# HomeAutomation.net
KiCad netlist of a schematic drawn in EAGLE
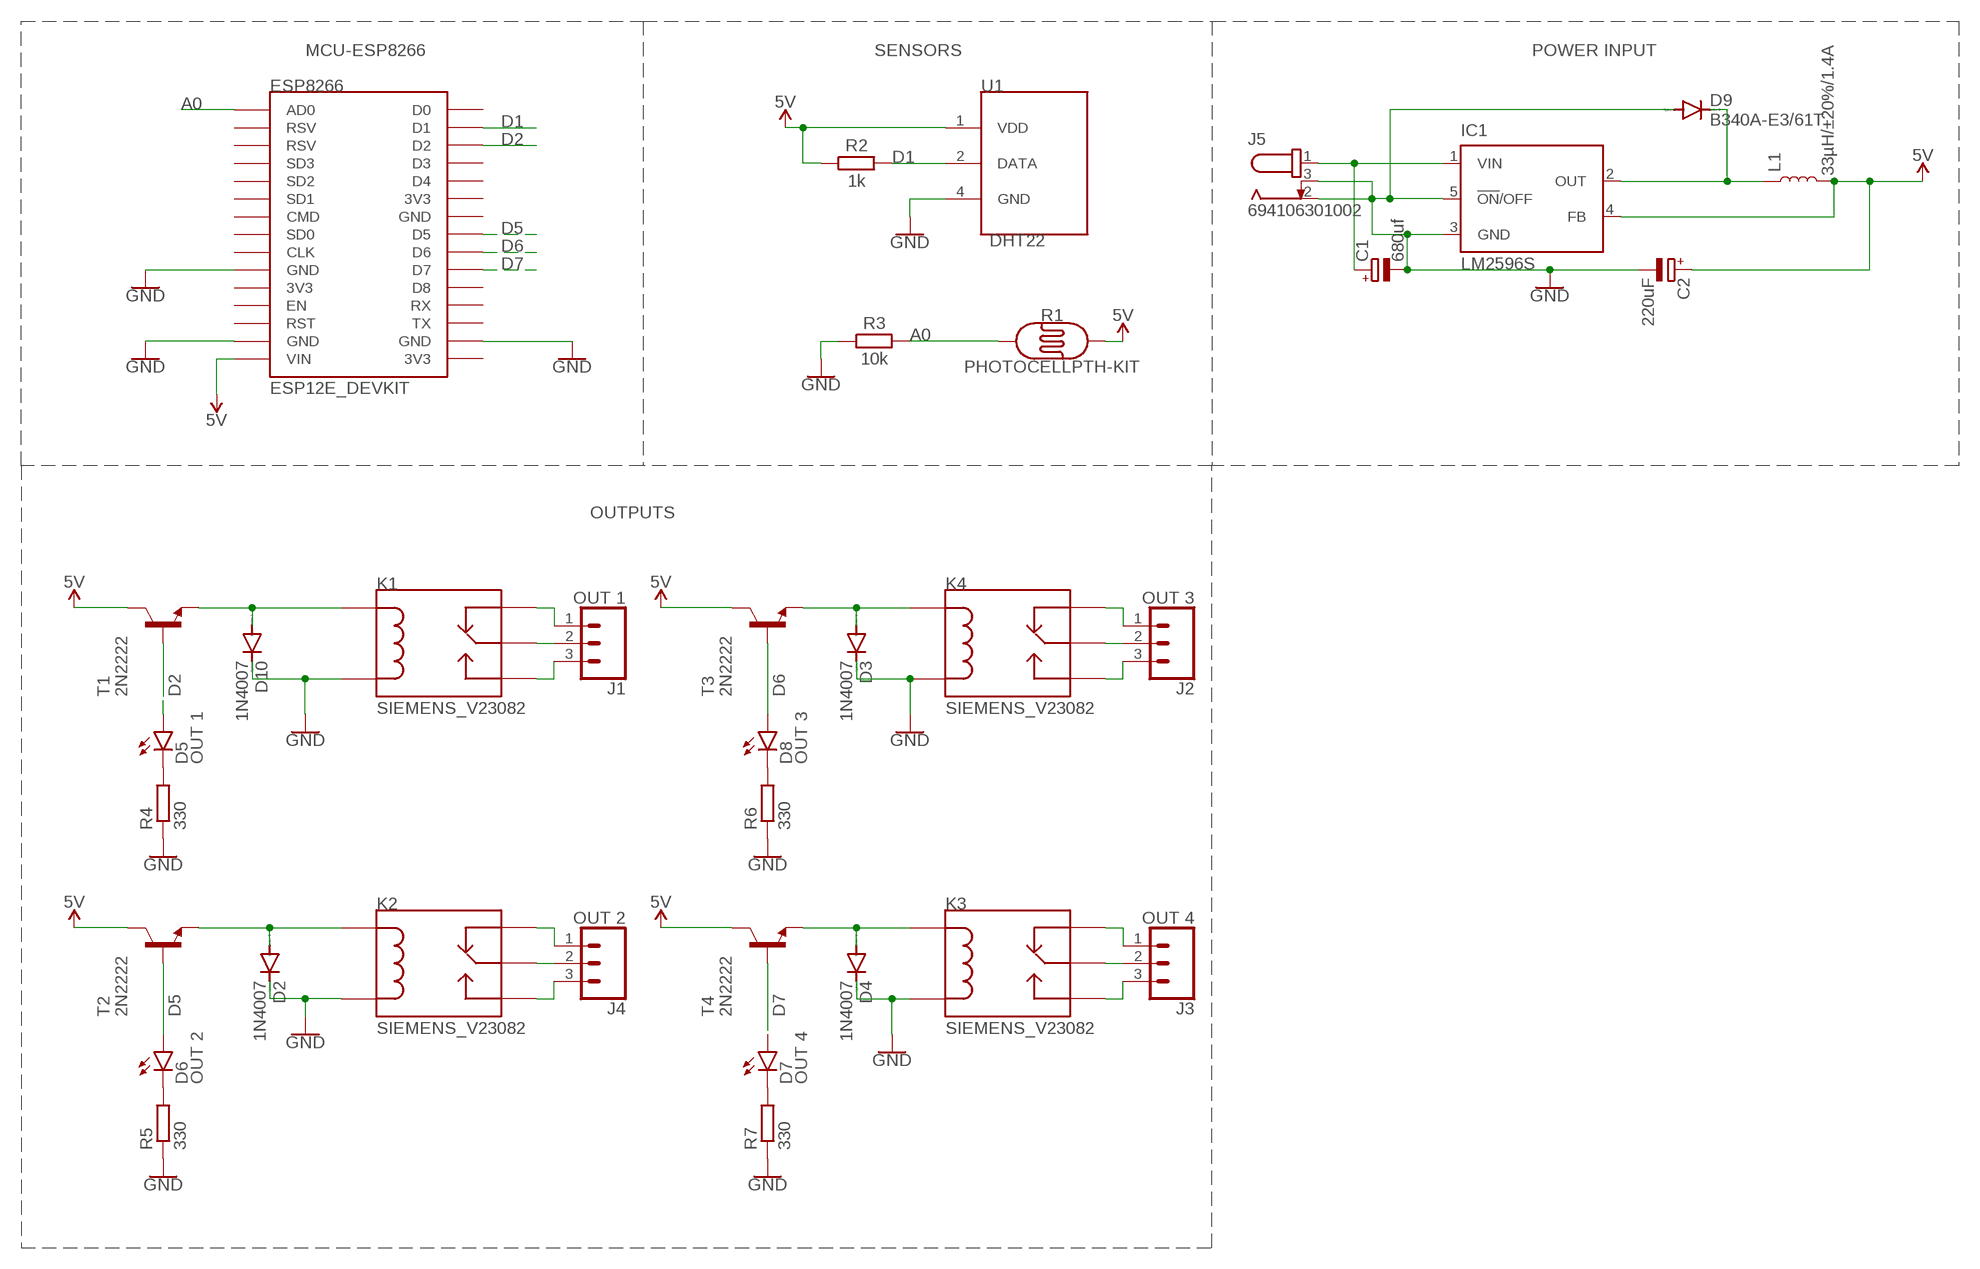
[diagram p0: schematic, sheet 1]

(export (version "E")
  (design (tool "Eeschema 10.0.6"))
  (components
    (comp (ref "C1")
      (value "680uf")
      (footprint "eagle-import:153CLV-0405")
      (libsource (lib "eagle-import") (part "CPOL-EU153CLV-0405"))
    )
    (comp (ref "C2")
      (value "220uF")
      (footprint "eagle-import:153CLV-0405")
      (libsource (lib "eagle-import") (part "CPOL-EU153CLV-0405"))
    )
    (comp (ref "D2")
      (value "1N4007")
      (footprint "eagle-import:DO214AC")
      (libsource (lib "eagle-import") (part "DIODE-DO214AC"))
    )
    (comp (ref "D3")
      (value "1N4007")
      (footprint "eagle-import:DO214AC")
      (libsource (lib "eagle-import") (part "DIODE-DO214AC"))
    )
    (comp (ref "D4")
      (value "1N4007")
      (footprint "eagle-import:DO214AC")
      (libsource (lib "eagle-import") (part "DIODE-DO214AC"))
    )
    (comp (ref "D5")
      (value "OUT 1")
      (footprint "eagle-import:CHIPLED_1206")
      (libsource (lib "eagle-import") (part "LEDCHIPLED_1206"))
    )
    (comp (ref "D6")
      (value "OUT 2")
      (footprint "eagle-import:CHIPLED_1206")
      (libsource (lib "eagle-import") (part "LEDCHIPLED_1206"))
    )
    (comp (ref "D7")
      (value "OUT 4")
      (footprint "eagle-import:CHIPLED_1206")
      (libsource (lib "eagle-import") (part "LEDCHIPLED_1206"))
    )
    (comp (ref "D8")
      (value "OUT 3")
      (footprint "eagle-import:CHIPLED_1206")
      (libsource (lib "eagle-import") (part "LEDCHIPLED_1206"))
    )
    (comp (ref "D9")
      (value "B340A-E3/61T")
      (footprint "eagle-import:DO214AC")
      (libsource (lib "eagle-import") (part "DIODE-DO214AC"))
    )
    (comp (ref "D10")
      (value "1N4007")
      (footprint "eagle-import:DO214AC")
      (libsource (lib "eagle-import") (part "DIODE-DO214AC"))
    )
    (comp (ref "ESP8266")
      (value "ESP12E_DEVKIT")
      (footprint "eagle-import:ESP12E_DEVKIT")
      (libsource (lib "eagle-import") (part "ESP12E_DEVKIT"))
    )
    (comp (ref "IC1")
      (value "LM2596S")
      (footprint "eagle-import:TO263-5")
      (fields (field (name "MF") "NATIONAL SEMICONDUCTOR") (field (name "MPN") "LM2596S-ADJ/NOPB"))
      (libsource (lib "eagle-import") (part "LM2596S"))
    )
    (comp (ref "J1")
      (value "OUT 1")
      (footprint "eagle-import:SCREWTERMINAL-5MM-3")
      (libsource (lib "eagle-import") (part "CONN_03-SCREW-5MM"))
    )
    (comp (ref "J2")
      (value "OUT 3")
      (footprint "eagle-import:SCREWTERMINAL-5MM-3")
      (libsource (lib "eagle-import") (part "CONN_03-SCREW-5MM"))
    )
    (comp (ref "J3")
      (value "OUT 4")
      (footprint "eagle-import:SCREWTERMINAL-5MM-3")
      (libsource (lib "eagle-import") (part "CONN_03-SCREW-5MM"))
    )
    (comp (ref "J4")
      (value "OUT 2")
      (footprint "eagle-import:SCREWTERMINAL-5MM-3")
      (libsource (lib "eagle-import") (part "CONN_03-SCREW-5MM"))
    )
    (comp (ref "J5")
      (value "694106301002")
      (footprint "eagle-import:694106301002")
      (fields
        (field (name "DIGIKEY_PART_NUMBER") "732-5930-ND")
        (field (name "MANUFACTURER") "Wurth Electronics Inc.")
        (field (name "CREATED_BY") "PCBLayout.com")
      )
      (libsource (lib "eagle-import") (part "694106301002"))
    )
    (comp (ref "K1")
      (value "SIEMENS_V23082")
      (footprint "eagle-import:SIEMENS_V23082_RELAY")
      (libsource (lib "eagle-import") (part "SIEMENS_V23082_RELAY"))
    )
    (comp (ref "K2")
      (value "SIEMENS_V23082")
      (footprint "eagle-import:SIEMENS_V23082_RELAY")
      (libsource (lib "eagle-import") (part "SIEMENS_V23082_RELAY"))
    )
    (comp (ref "K3")
      (value "SIEMENS_V23082")
      (footprint "eagle-import:SIEMENS_V23082_RELAY")
      (libsource (lib "eagle-import") (part "SIEMENS_V23082_RELAY"))
    )
    (comp (ref "K4")
      (value "SIEMENS_V23082")
      (footprint "eagle-import:SIEMENS_V23082_RELAY")
      (libsource (lib "eagle-import") (part "SIEMENS_V23082_RELAY"))
    )
    (comp (ref "L1")
      (value "33µH/±20%/1.4A")
      (footprint "eagle-import:SRN6045")
      (libsource (lib "eagle-import") (part "INDUCTOR-SRN6045-33UH"))
    )
    (comp (ref "R1")
      (value "PHOTOCELLPTH-KIT")
      (footprint "eagle-import:PHOTOCELL-KIT")
      (libsource (lib "eagle-import") (part "PHOTOCELLPTH-KIT"))
    )
    (comp (ref "R2")
      (value "1k")
      (footprint "eagle-import:RESC1005X40")
      (libsource (lib "eagle-import") (part "RCHIP-0402(1005-METRIC)_"))
    )
    (comp (ref "R3")
      (value "10k")
      (footprint "eagle-import:RESC1005X40")
      (libsource (lib "eagle-import") (part "RCHIP-0402(1005-METRIC)_"))
    )
    (comp (ref "R4")
      (value "330")
      (footprint "eagle-import:R0805")
      (libsource (lib "eagle-import") (part "R-EU_R0805"))
    )
    (comp (ref "R5")
      (value "330")
      (footprint "eagle-import:R0805")
      (libsource (lib "eagle-import") (part "R-EU_R0805"))
    )
    (comp (ref "R6")
      (value "330")
      (footprint "eagle-import:R0805")
      (libsource (lib "eagle-import") (part "R-EU_R0805"))
    )
    (comp (ref "R7")
      (value "330")
      (footprint "eagle-import:R0805")
      (libsource (lib "eagle-import") (part "R-EU_R0805"))
    )
    (comp (ref "T1")
      (value "2N2222")
      (footprint "eagle-import:SOT23-BEC")
      (libsource (lib "eagle-import") (part "-NPN-SOT23-BECMMBT2222ALT1"))
    )
    (comp (ref "T2")
      (value "2N2222")
      (footprint "eagle-import:SOT23-BEC")
      (libsource (lib "eagle-import") (part "-NPN-SOT23-BECMMBT2222ALT1"))
    )
    (comp (ref "T3")
      (value "2N2222")
      (footprint "eagle-import:SOT23-BEC")
      (libsource (lib "eagle-import") (part "-NPN-SOT23-BECMMBT2222ALT1"))
    )
    (comp (ref "T4")
      (value "2N2222")
      (footprint "eagle-import:SOT23-BEC")
      (libsource (lib "eagle-import") (part "-NPN-SOT23-BECMMBT2222ALT1"))
    )
    (comp (ref "U1")
      (value "DHT22")
      (footprint "eagle-import:DHT22")
      (libsource (lib "eagle-import") (part "DHT22"))
    )
  )
  (nets
    (net (code "1") (name "/A0") (class "Default")
      (node (ref "ESP8266") (pin "AD0") (pinfunction "AD0_AD0") (pintype "bidirectional"))
      (node (ref "R1") (pin "1") (pinfunction "P$1_1") (pintype "bidirectional"))
      (node (ref "R3") (pin "2") (pinfunction "2_2") (pintype "passive"))
    )
    (net (code "2") (name "/D1") (class "Default")
      (node (ref "ESP8266") (pin "D1") (pinfunction "D1_D1") (pintype "bidirectional"))
      (node (ref "R2") (pin "2") (pinfunction "2_2") (pintype "passive"))
      (node (ref "U1") (pin "2") (pinfunction "DATA_2") (pintype "bidirectional"))
    )
    (net (code "3") (name "/D2") (class "Default")
      (node (ref "D5") (pin "A") (pinfunction "A_A") (pintype "passive"))
      (node (ref "ESP8266") (pin "D2") (pinfunction "D2_D2") (pintype "bidirectional"))
      (node (ref "T1") (pin "B") (pinfunction "B_B") (pintype "passive"))
    )
    (net (code "4") (name "/D5") (class "Default")
      (node (ref "D6") (pin "A") (pinfunction "A_A") (pintype "passive"))
      (node (ref "ESP8266") (pin "D5") (pinfunction "D5_D5") (pintype "bidirectional"))
      (node (ref "T2") (pin "B") (pinfunction "B_B") (pintype "passive"))
    )
    (net (code "5") (name "/D6") (class "Default")
      (node (ref "D8") (pin "A") (pinfunction "A_A") (pintype "passive"))
      (node (ref "ESP8266") (pin "D6") (pinfunction "D6_D6") (pintype "bidirectional"))
      (node (ref "T3") (pin "B") (pinfunction "B_B") (pintype "passive"))
    )
    (net (code "6") (name "/D7") (class "Default")
      (node (ref "D7") (pin "A") (pinfunction "A_A") (pintype "passive"))
      (node (ref "ESP8266") (pin "D7") (pinfunction "D7_D7") (pintype "bidirectional"))
      (node (ref "T4") (pin "B") (pinfunction "B_B") (pintype "passive"))
    )
    (net (code "7") (name "5V") (class "Default")
      (node (ref "C2") (pin "+") (pinfunction "+_+") (pintype "passive"))
      (node (ref "ESP8266") (pin "VIN") (pinfunction "VIN_VIN") (pintype "bidirectional"))
      (node (ref "IC1") (pin "4") (pinfunction "FB_4") (pintype "input"))
      (node (ref "L1") (pin "2") (pinfunction "2_2") (pintype "passive"))
      (node (ref "R1") (pin "2") (pinfunction "P$2_2") (pintype "bidirectional"))
      (node (ref "R2") (pin "1") (pinfunction "1_1") (pintype "passive"))
      (node (ref "T1") (pin "C") (pinfunction "C_C") (pintype "passive"))
      (node (ref "T2") (pin "C") (pinfunction "C_C") (pintype "passive"))
      (node (ref "T3") (pin "C") (pinfunction "C_C") (pintype "passive"))
      (node (ref "T4") (pin "C") (pinfunction "C_C") (pintype "passive"))
      (node (ref "U1") (pin "1") (pinfunction "VDD_1") (pintype "bidirectional"))
    )
    (net (code "8") (name "GND") (class "Default")
      (node (ref "C1") (pin "-") (pinfunction "-_-") (pintype "passive"))
      (node (ref "C2") (pin "-") (pinfunction "-_-") (pintype "passive"))
      (node (ref "D10") (pin "C") (pinfunction "C_C") (pintype "passive"))
      (node (ref "D2") (pin "C") (pinfunction "C_C") (pintype "passive"))
      (node (ref "D3") (pin "C") (pinfunction "C_C") (pintype "passive"))
      (node (ref "D4") (pin "C") (pinfunction "C_C") (pintype "passive"))
      (node (ref "D9") (pin "A") (pinfunction "A_A") (pintype "passive"))
      (node (ref "ESP8266") (pin "GND@0") (pinfunction "GND_GND@0") (pintype "bidirectional"))
      (node (ref "ESP8266") (pin "GND@1") (pinfunction "GND_GND@1") (pintype "bidirectional"))
      (node (ref "ESP8266") (pin "GND@3") (pinfunction "GND_GND@3") (pintype "bidirectional"))
      (node (ref "IC1") (pin "3") (pinfunction "GND_3") (pintype "power_in"))
      (node (ref "IC1") (pin "5") (pinfunction "~{ON}/OFF_5") (pintype "input"))
      (node (ref "J5") (pin "2") (pinfunction "2_2") (pintype "passive"))
      (node (ref "J5") (pin "3") (pinfunction "3_3") (pintype "passive"))
      (node (ref "K1") (pin "P$2") (pinfunction "P$2_P$2") (pintype "bidirectional"))
      (node (ref "K2") (pin "P$2") (pinfunction "P$2_P$2") (pintype "bidirectional"))
      (node (ref "K3") (pin "P$2") (pinfunction "P$2_P$2") (pintype "bidirectional"))
      (node (ref "K4") (pin "P$2") (pinfunction "P$2_P$2") (pintype "bidirectional"))
      (node (ref "R3") (pin "1") (pinfunction "1_1") (pintype "passive"))
      (node (ref "R4") (pin "1") (pinfunction "1_1") (pintype "passive"))
      (node (ref "R5") (pin "1") (pinfunction "1_1") (pintype "passive"))
      (node (ref "R6") (pin "1") (pinfunction "1_1") (pintype "passive"))
      (node (ref "R7") (pin "1") (pinfunction "1_1") (pintype "passive"))
      (node (ref "U1") (pin "4") (pinfunction "GND_4") (pintype "bidirectional"))
    )
    (net (code "9") (name "Net-(D2-PadA)") (class "Default")
      (node (ref "D2") (pin "A") (pinfunction "A_A") (pintype "passive"))
      (node (ref "K2") (pin "P$1") (pinfunction "P$1_P$1") (pintype "bidirectional"))
      (node (ref "T2") (pin "E") (pinfunction "E_E") (pintype "passive"))
    )
    (net (code "10") (name "Net-(D3-PadA)") (class "Default")
      (node (ref "D3") (pin "A") (pinfunction "A_A") (pintype "passive"))
      (node (ref "K4") (pin "P$1") (pinfunction "P$1_P$1") (pintype "bidirectional"))
      (node (ref "T3") (pin "E") (pinfunction "E_E") (pintype "passive"))
    )
    (net (code "11") (name "Net-(D4-PadA)") (class "Default")
      (node (ref "D4") (pin "A") (pinfunction "A_A") (pintype "passive"))
      (node (ref "K3") (pin "P$1") (pinfunction "P$1_P$1") (pintype "bidirectional"))
      (node (ref "T4") (pin "E") (pinfunction "E_E") (pintype "passive"))
    )
    (net (code "12") (name "Net-(D5-PadC)") (class "Default")
      (node (ref "D5") (pin "C") (pinfunction "C_C") (pintype "passive"))
      (node (ref "R4") (pin "2") (pinfunction "2_2") (pintype "passive"))
    )
    (net (code "13") (name "Net-(D6-PadC)") (class "Default")
      (node (ref "D6") (pin "C") (pinfunction "C_C") (pintype "passive"))
      (node (ref "R5") (pin "2") (pinfunction "2_2") (pintype "passive"))
    )
    (net (code "14") (name "Net-(D7-PadC)") (class "Default")
      (node (ref "D7") (pin "C") (pinfunction "C_C") (pintype "passive"))
      (node (ref "R7") (pin "2") (pinfunction "2_2") (pintype "passive"))
    )
    (net (code "15") (name "Net-(D8-PadC)") (class "Default")
      (node (ref "D8") (pin "C") (pinfunction "C_C") (pintype "passive"))
      (node (ref "R6") (pin "2") (pinfunction "2_2") (pintype "passive"))
    )
    (net (code "16") (name "Net-(D10-PadA)") (class "Default")
      (node (ref "D10") (pin "A") (pinfunction "A_A") (pintype "passive"))
      (node (ref "K1") (pin "P$1") (pinfunction "P$1_P$1") (pintype "bidirectional"))
      (node (ref "T1") (pin "E") (pinfunction "E_E") (pintype "passive"))
    )
    (net (code "17") (name "Net-(IC1-OUT)") (class "Default")
      (node (ref "D9") (pin "C") (pinfunction "C_C") (pintype "passive"))
      (node (ref "IC1") (pin "2") (pinfunction "OUT_2") (pintype "output"))
      (node (ref "L1") (pin "1") (pinfunction "1_1") (pintype "passive"))
    )
    (net (code "18") (name "Net-(IC1-VIN)") (class "Default")
      (node (ref "C1") (pin "+") (pinfunction "+_+") (pintype "passive"))
      (node (ref "IC1") (pin "1") (pinfunction "VIN_1") (pintype "input"))
      (node (ref "J5") (pin "1") (pinfunction "1_1") (pintype "passive"))
    )
    (net (code "19") (name "Net-(J1-Pad1)") (class "Default")
      (node (ref "J1") (pin "1") (pinfunction "1_1") (pintype "passive"))
      (node (ref "K1") (pin "P$5") (pinfunction "P$5_P$5") (pintype "bidirectional"))
    )
    (net (code "20") (name "Net-(J1-Pad2)") (class "Default")
      (node (ref "J1") (pin "2") (pinfunction "2_2") (pintype "passive"))
      (node (ref "K1") (pin "P$3") (pinfunction "P$3_P$3") (pintype "bidirectional"))
    )
    (net (code "21") (name "Net-(J1-Pad3)") (class "Default")
      (node (ref "J1") (pin "3") (pinfunction "3_3") (pintype "passive"))
      (node (ref "K1") (pin "P$4") (pinfunction "P$4_P$4") (pintype "bidirectional"))
    )
    (net (code "22") (name "Net-(J2-Pad1)") (class "Default")
      (node (ref "J2") (pin "1") (pinfunction "1_1") (pintype "passive"))
      (node (ref "K4") (pin "P$5") (pinfunction "P$5_P$5") (pintype "bidirectional"))
    )
    (net (code "23") (name "Net-(J2-Pad2)") (class "Default")
      (node (ref "J2") (pin "2") (pinfunction "2_2") (pintype "passive"))
      (node (ref "K4") (pin "P$3") (pinfunction "P$3_P$3") (pintype "bidirectional"))
    )
    (net (code "24") (name "Net-(J2-Pad3)") (class "Default")
      (node (ref "J2") (pin "3") (pinfunction "3_3") (pintype "passive"))
      (node (ref "K4") (pin "P$4") (pinfunction "P$4_P$4") (pintype "bidirectional"))
    )
    (net (code "25") (name "Net-(J3-Pad1)") (class "Default")
      (node (ref "J3") (pin "1") (pinfunction "1_1") (pintype "passive"))
      (node (ref "K3") (pin "P$5") (pinfunction "P$5_P$5") (pintype "bidirectional"))
    )
    (net (code "26") (name "Net-(J3-Pad2)") (class "Default")
      (node (ref "J3") (pin "2") (pinfunction "2_2") (pintype "passive"))
      (node (ref "K3") (pin "P$3") (pinfunction "P$3_P$3") (pintype "bidirectional"))
    )
    (net (code "27") (name "Net-(J3-Pad3)") (class "Default")
      (node (ref "J3") (pin "3") (pinfunction "3_3") (pintype "passive"))
      (node (ref "K3") (pin "P$4") (pinfunction "P$4_P$4") (pintype "bidirectional"))
    )
    (net (code "28") (name "Net-(J4-Pad1)") (class "Default")
      (node (ref "J4") (pin "1") (pinfunction "1_1") (pintype "passive"))
      (node (ref "K2") (pin "P$5") (pinfunction "P$5_P$5") (pintype "bidirectional"))
    )
    (net (code "29") (name "Net-(J4-Pad2)") (class "Default")
      (node (ref "J4") (pin "2") (pinfunction "2_2") (pintype "passive"))
      (node (ref "K2") (pin "P$3") (pinfunction "P$3_P$3") (pintype "bidirectional"))
    )
    (net (code "30") (name "Net-(J4-Pad3)") (class "Default")
      (node (ref "J4") (pin "3") (pinfunction "3_3") (pintype "passive"))
      (node (ref "K2") (pin "P$4") (pinfunction "P$4_P$4") (pintype "bidirectional"))
    )
    (net (code "31") (name "unconnected-(ESP8266-3V3-Pad3V3@0)") (class "Default")
      (node (ref "ESP8266") (pin "3V3@0") (pinfunction "3V3_3V3@0") (pintype "bidirectional"))
    )
    (net (code "32") (name "unconnected-(ESP8266-3V3-Pad3V3@1)") (class "Default")
      (node (ref "ESP8266") (pin "3V3@1") (pinfunction "3V3_3V3@1") (pintype "bidirectional"))
    )
    (net (code "33") (name "unconnected-(ESP8266-3V3-Pad3V3@2)") (class "Default")
      (node (ref "ESP8266") (pin "3V3@2") (pinfunction "3V3_3V3@2") (pintype "bidirectional"))
    )
    (net (code "34") (name "unconnected-(ESP8266-GND-PadGND@2)") (class "Default")
      (node (ref "ESP8266") (pin "GND@2") (pinfunction "GND_GND@2") (pintype "bidirectional"))
    )
    (net (code "35") (name "unconnected-(ESP8266-PadCLK)") (class "Default")
      (node (ref "ESP8266") (pin "CLK") (pinfunction "CLK_CLK") (pintype "bidirectional"))
    )
    (net (code "36") (name "unconnected-(ESP8266-PadCMD)") (class "Default")
      (node (ref "ESP8266") (pin "CMD") (pinfunction "CMD_CMD") (pintype "bidirectional"))
    )
    (net (code "37") (name "unconnected-(ESP8266-PadD0)") (class "Default")
      (node (ref "ESP8266") (pin "D0") (pinfunction "D0_D0") (pintype "bidirectional"))
    )
    (net (code "38") (name "unconnected-(ESP8266-PadD3)") (class "Default")
      (node (ref "ESP8266") (pin "D3") (pinfunction "D3_D3") (pintype "bidirectional"))
    )
    (net (code "39") (name "unconnected-(ESP8266-PadD4)") (class "Default")
      (node (ref "ESP8266") (pin "D4") (pinfunction "D4_D4") (pintype "bidirectional"))
    )
    (net (code "40") (name "unconnected-(ESP8266-PadD8)") (class "Default")
      (node (ref "ESP8266") (pin "D8") (pinfunction "D8_D8") (pintype "bidirectional"))
    )
    (net (code "41") (name "unconnected-(ESP8266-PadEN)") (class "Default")
      (node (ref "ESP8266") (pin "EN") (pinfunction "EN_EN") (pintype "bidirectional"))
    )
    (net (code "42") (name "unconnected-(ESP8266-PadRST)") (class "Default")
      (node (ref "ESP8266") (pin "RST") (pinfunction "RST_RST") (pintype "bidirectional"))
    )
    (net (code "43") (name "unconnected-(ESP8266-PadRX)") (class "Default")
      (node (ref "ESP8266") (pin "RX") (pinfunction "RX_RX") (pintype "bidirectional"))
    )
    (net (code "44") (name "unconnected-(ESP8266-PadSD0)") (class "Default")
      (node (ref "ESP8266") (pin "SD0") (pinfunction "SD0_SD0") (pintype "bidirectional"))
    )
    (net (code "45") (name "unconnected-(ESP8266-PadSD1)") (class "Default")
      (node (ref "ESP8266") (pin "SD1") (pinfunction "SD1_SD1") (pintype "bidirectional"))
    )
    (net (code "46") (name "unconnected-(ESP8266-PadSD2)") (class "Default")
      (node (ref "ESP8266") (pin "SD2") (pinfunction "SD2_SD2") (pintype "bidirectional"))
    )
    (net (code "47") (name "unconnected-(ESP8266-PadSD3)") (class "Default")
      (node (ref "ESP8266") (pin "SD3") (pinfunction "SD3_SD3") (pintype "bidirectional"))
    )
    (net (code "48") (name "unconnected-(ESP8266-PadTX)") (class "Default")
      (node (ref "ESP8266") (pin "TX") (pinfunction "TX_TX") (pintype "bidirectional"))
    )
    (net (code "49") (name "unconnected-(ESP8266-RSV-PadRSV@0)") (class "Default")
      (node (ref "ESP8266") (pin "RSV@0") (pinfunction "RSV_RSV@0") (pintype "bidirectional"))
    )
    (net (code "50") (name "unconnected-(ESP8266-RSV-PadRSV@1)") (class "Default")
      (node (ref "ESP8266") (pin "RSV@1") (pinfunction "RSV_RSV@1") (pintype "bidirectional"))
    )
  )
)
